# rs485.net
KiCad netlist of a schematic drawn in EasyEDA
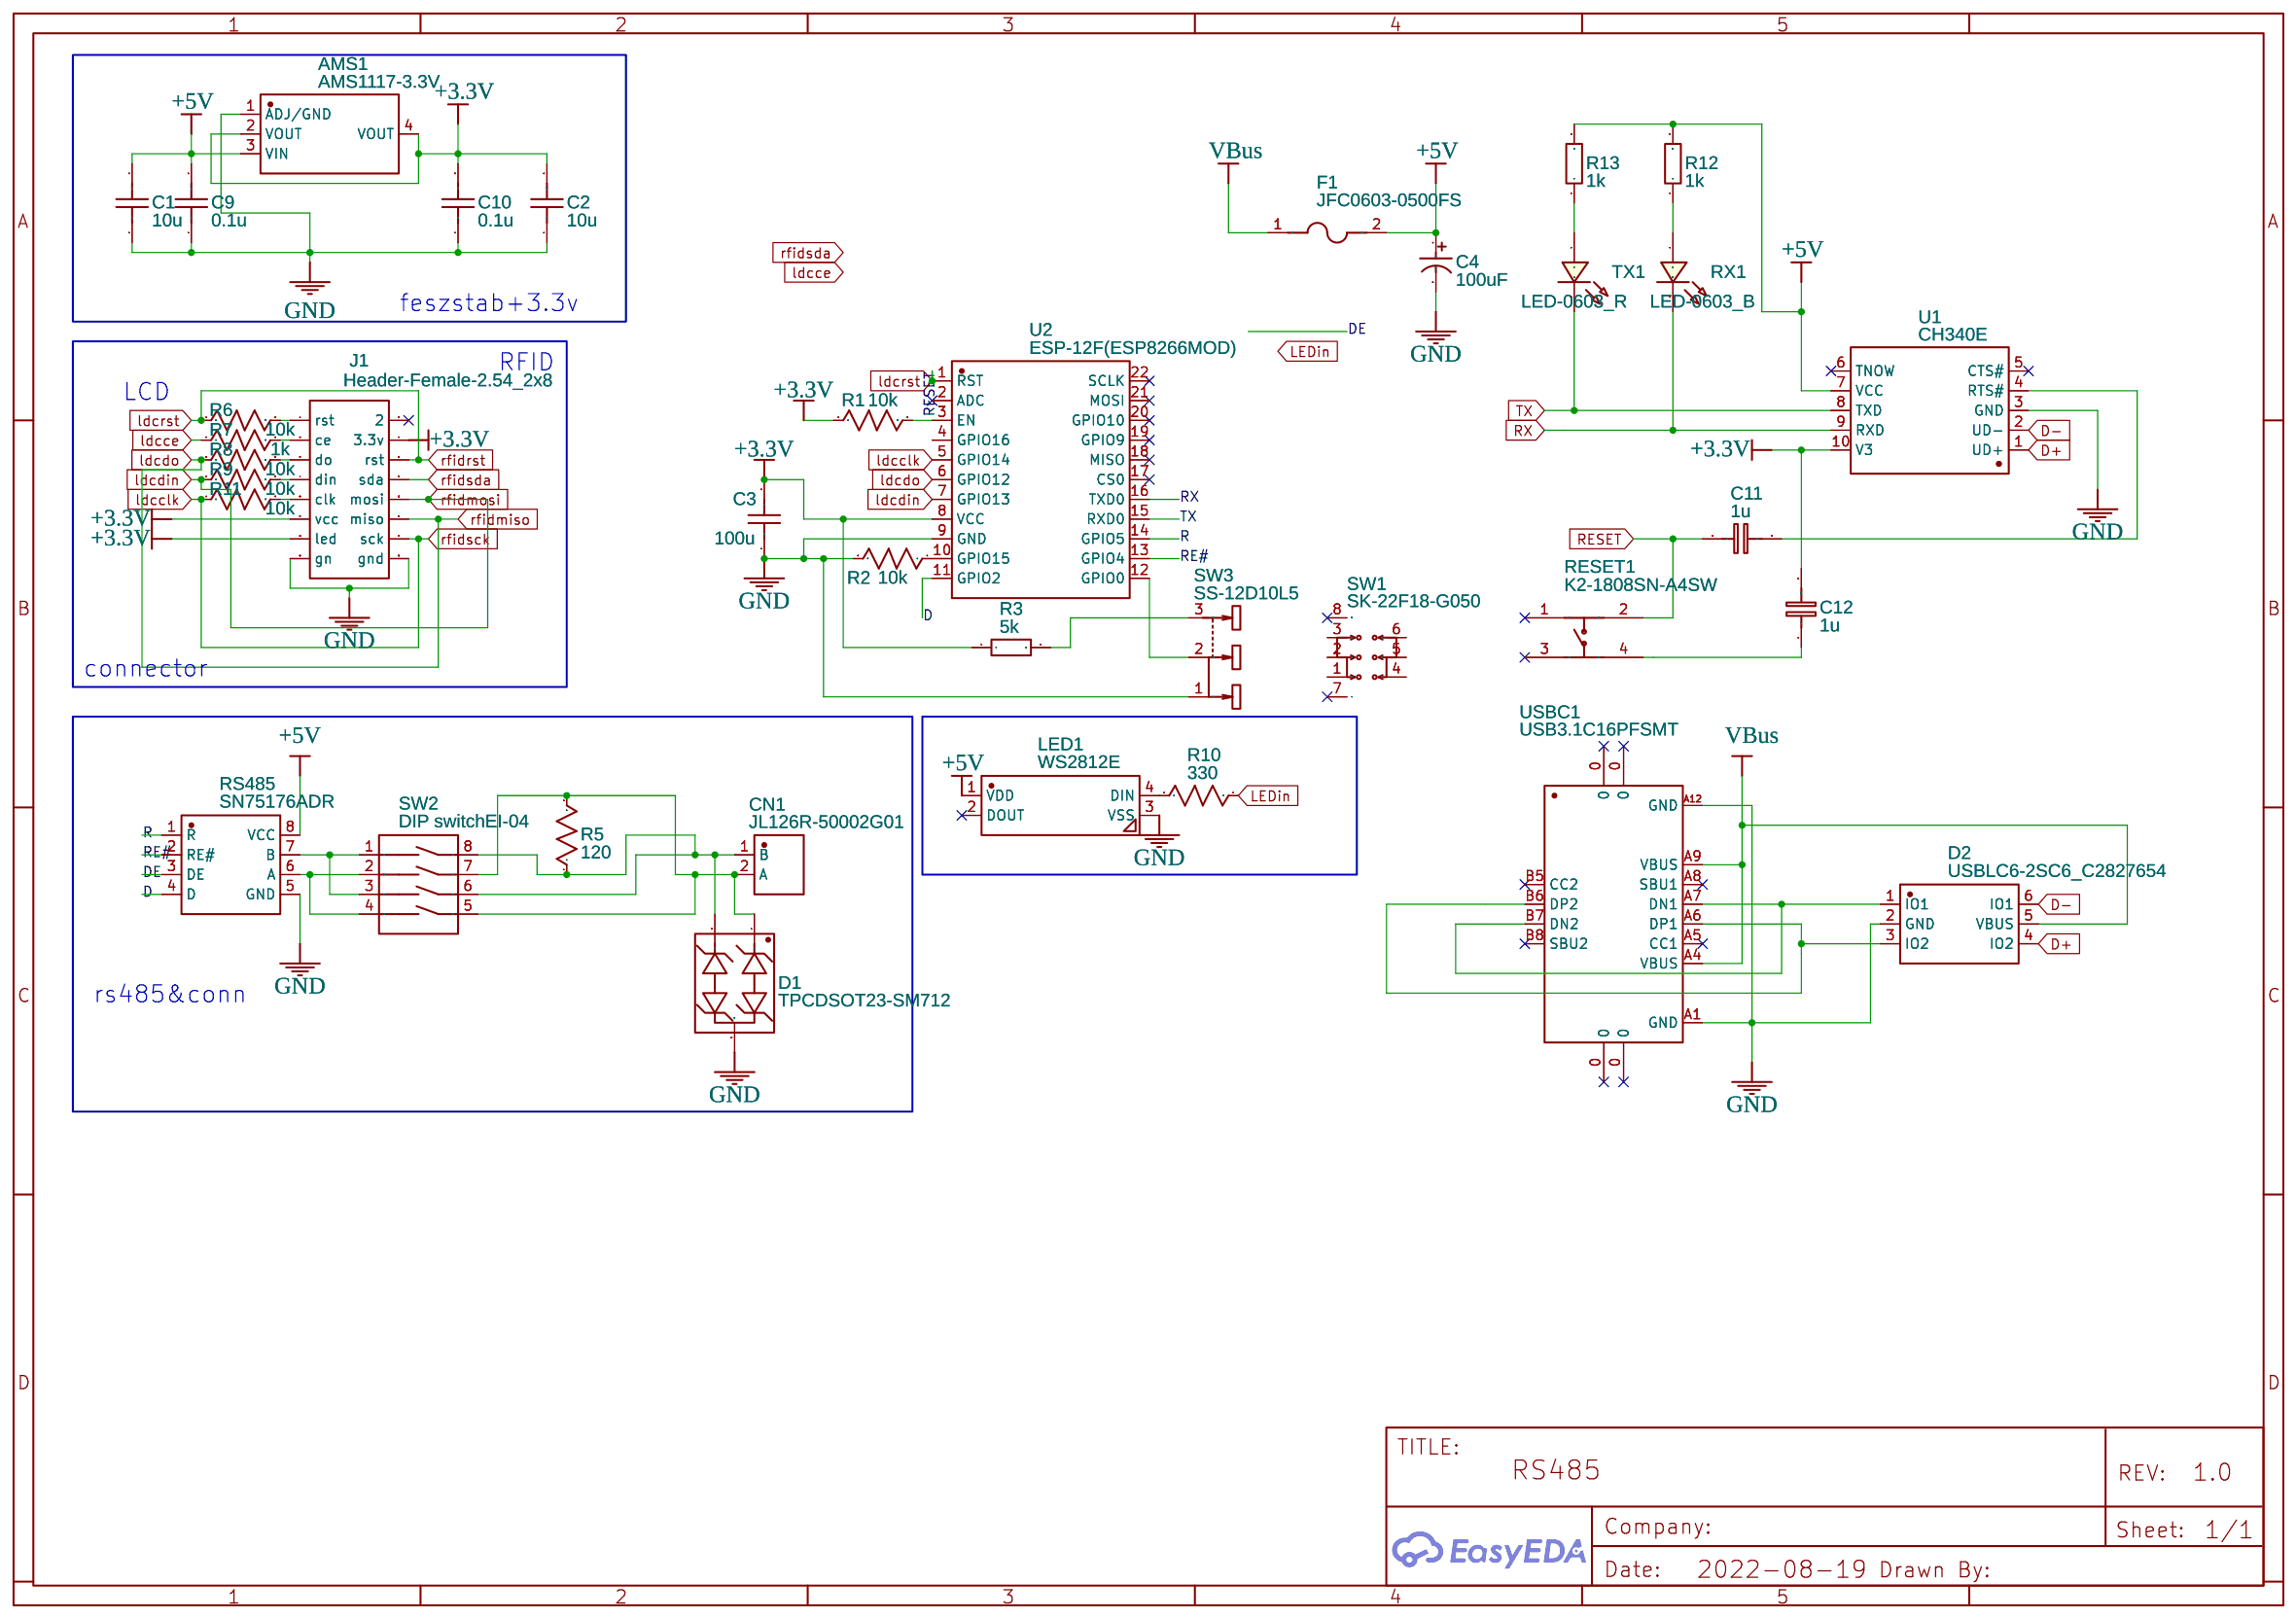
[diagram p0: schematic sheet]

(export (version "E")
  (design (tool "Eeschema 10.0.6"))
  (components
    (comp (ref "AMS1")
      (value "AMS1117-3.3V")
      (fields (field (name "BOM_Supplier Part") "C2688239"))
      (libsource (lib "") (part "AMS1117-3.3V"))
    )
    (comp (ref "C1") (value "10u") (libsource (lib "") (part "C_0603_US")))
    (comp (ref "C2") (value "10u") (libsource (lib "") (part "C_0603_US")))
    (comp (ref "C3") (value "100u") (libsource (lib "") (part "C_0603_US")))
    (comp (ref "C4")
      (value "100uF")
      (fields
        (field (name "BOM_Manufacturer Part") "RVT1A101M0505")
        (field (name "BOM_Supplier Part") "C3347")
      )
      (libsource (lib "") (part "RVT1A101M0505-C3347"))
    )
    (comp (ref "C9") (value "0.1u") (libsource (lib "") (part "C_0603_US")))
    (comp (ref "C10") (value "0.1u") (libsource (lib "") (part "C_0603_US")))
    (comp (ref "C11")
      (value "1u")
      (fields (field (name "BOM_Manufacturer Part") "?"))
      (libsource (lib "") (part "Cap_0603_EU_1"))
    )
    (comp (ref "C12")
      (value "1u")
      (fields (field (name "BOM_Manufacturer Part") "?"))
      (libsource (lib "") (part "Cap_0603_EU"))
    )
    (comp (ref "CN1")
      (value "JL126R-50002G01")
      (fields (field (name "BOM_Supplier Part") "C415452"))
      (libsource (lib "") (part "JL126R-50002G01"))
    )
    (comp (ref "D1")
      (value "TPCDSOT23-SM712")
      (fields (field (name "BOM_Supplier Part") "C558433"))
      (libsource (lib "") (part "TPCDSOT23-SM712"))
    )
    (comp (ref "D2")
      (value "USBLC6-2SC6_C2827654")
      (fields
        (field (name "BOM_Manufacturer Part") "USBLC6-2SC6")
        (field (name "BOM_Supplier Part") "C2827654")
      )
      (libsource (lib "") (part "USBLC6-2SC6_C2827654"))
    )
    (comp (ref "F1")
      (value "JFC0603-0500FS")
      (fields (field (name "BOM_Supplier Part") "C136327"))
      (libsource (lib "") (part "JFC0603-0500FS"))
    )
    (comp (ref "J1")
      (value "Header-Female-2.54_2x8")
      (fields
        (field (name "BOM_Manufacturer Part") "2.54mm,2×8Double female header")
        (field (name "BOM_Supplier Part") "C30734")
      )
      (libsource (lib "") (part "Header-Female-2.54_2x8"))
    )
    (comp (ref "LED1")
      (value "WS2812E")
      (fields (field (name "BOM_Supplier Part") "C139127"))
      (libsource (lib "") (part "WS2812E"))
    )
    (comp (ref "R1") (value "10k") (libsource (lib "") (part "R_0603_US_1")))
    (comp (ref "R2") (value "10k") (libsource (lib "") (part "R_0603_US")))
    (comp (ref "R3")
      (value "5k")
      (fields
        (field (name "BOM_Manufacturer Part") "RS-03K102JT")
        (field (name "BOM_Supplier Part") "C73797")
      )
      (libsource (lib "") (part "RS-03K102JT_1"))
    )
    (comp (ref "R5") (value "120") (libsource (lib "") (part "R_0603_US_2")))
    (comp (ref "R6") (value "10k") (libsource (lib "") (part "R_0603_US_1")))
    (comp (ref "R7") (value "1k") (libsource (lib "") (part "R_0603_US_1")))
    (comp (ref "R8") (value "10k") (libsource (lib "") (part "R_0603_US_1")))
    (comp (ref "R9") (value "10k") (libsource (lib "") (part "R_0603_US_1")))
    (comp (ref "R10") (value "330") (libsource (lib "") (part "R_0603_US_1")))
    (comp (ref "R11") (value "10k") (libsource (lib "") (part "R_0603_US_1")))
    (comp (ref "R12")
      (value "1k")
      (fields
        (field (name "BOM_Manufacturer Part") "RS-03K102JT")
        (field (name "BOM_Supplier Part") "C73797")
      )
      (libsource (lib "") (part "RS-03K102JT"))
    )
    (comp (ref "R13")
      (value "1k")
      (fields
        (field (name "BOM_Manufacturer Part") "RS-03K102JT")
        (field (name "BOM_Supplier Part") "C73797")
      )
      (libsource (lib "") (part "RS-03K102JT"))
    )
    (comp (ref "RESET1")
      (value "K2-1808SN-A4SW")
      (fields (field (name "BOM_Supplier Part") "C92589"))
      (libsource (lib "") (part "K2-1808SN-A4SW"))
    )
    (comp (ref "RS485")
      (value "SN75176ADR")
      (fields (field (name "BOM_Supplier Part") "C468242"))
      (libsource (lib "") (part "SN75176ADR"))
    )
    (comp (ref "RX1")
      (value "LED-0603_B")
      (fields
        (field (name "BOM_Manufacturer Part") "19-217/BHC-ZL1M2RY/3T")
        (field (name "BOM_Supplier Part") "C72041")
      )
      (libsource (lib "") (part "LED-0603_B"))
    )
    (comp (ref "SW1")
      (value "SK-22F18-G050")
      (fields (field (name "BOM_Supplier Part") "C2848886"))
      (libsource (lib "") (part "SK-22F18-G050"))
    )
    (comp (ref "SW2")
      (value "DIP switchEI-04")
      (fields (field (name "BOM_Supplier Part") "C99987"))
      (libsource (lib "") (part "DIP switchEI-04"))
    )
    (comp (ref "SW3")
      (value "SS-12D10L5")
      (fields (field (name "BOM_Supplier Part") "C319012"))
      (libsource (lib "") (part "SS-12D10L5"))
    )
    (comp (ref "TX1")
      (value "LED-0603_R")
      (fields
        (field (name "BOM_Manufacturer Part") "19-217/R6C-AL1M2VY/3T")
        (field (name "BOM_Supplier Part") "C72044")
      )
      (libsource (lib "") (part "LED-0603_R"))
    )
    (comp (ref "U1")
      (value "CH340E")
      (fields (field (name "BOM_Supplier Part") "C99652"))
      (libsource (lib "") (part "CH340E"))
    )
    (comp (ref "U2")
      (value "ESP-12F(ESP8266MOD)")
      (fields (field (name "BOM_Supplier Part") "C82891"))
      (libsource (lib "") (part "ESP-12F(ESP8266MOD)"))
    )
    (comp (ref "USBC1")
      (value "USB3.1C16PFSMT")
      (fields (field (name "BOM_Supplier Part") "C167321"))
      (libsource (lib "") (part "USB3.1C16PFSMT"))
    )
  )
  (nets
    (net (code "1") (name "+3.3V") (class "Default")
      (node (ref "AMS1") (pin "2") (pinfunction "VOUT_2") (pintype "unspecified"))
      (node (ref "AMS1") (pin "4") (pinfunction "VOUT_4") (pintype "unspecified"))
      (node (ref "C10") (pin "2") (pinfunction "2_2") (pintype "unspecified"))
      (node (ref "C12") (pin "2") (pinfunction "2_2") (pintype "unspecified"))
      (node (ref "C2") (pin "2") (pinfunction "2_2") (pintype "unspecified"))
      (node (ref "C3") (pin "2") (pinfunction "2_2") (pintype "unspecified"))
      (node (ref "J1") (pin "11") (pinfunction "vcc_11") (pintype "input"))
      (node (ref "J1") (pin "13") (pinfunction "led_13") (pintype "input"))
      (node (ref "J1") (pin "4") (pinfunction "3.3v_4") (pintype "input"))
      (node (ref "R1") (pin "1") (pinfunction "1_1") (pintype "unspecified"))
      (node (ref "R3") (pin "1") (pinfunction "1_1") (pintype "input"))
      (node (ref "U1") (pin "10") (pinfunction "V3_10") (pintype "unspecified"))
      (node (ref "U2") (pin "8") (pinfunction "VCC_8") (pintype "unspecified"))
    )
    (net (code "2") (name "+5V") (class "Default")
      (node (ref "AMS1") (pin "3") (pinfunction "VIN_3") (pintype "unspecified"))
      (node (ref "C1") (pin "2") (pinfunction "2_2") (pintype "unspecified"))
      (node (ref "C4") (pin "1") (pinfunction "1_1") (pintype "input"))
      (node (ref "C9") (pin "2") (pinfunction "2_2") (pintype "unspecified"))
      (node (ref "F1") (pin "2") (pinfunction "2_2") (pintype "unspecified"))
      (node (ref "LED1") (pin "1") (pinfunction "VDD_1") (pintype "unspecified"))
      (node (ref "R12") (pin "2") (pinfunction "2_2") (pintype "input"))
      (node (ref "R13") (pin "2") (pinfunction "2_2") (pintype "input"))
      (node (ref "RS485") (pin "8") (pinfunction "VCC_8") (pintype "unspecified"))
      (node (ref "U1") (pin "7") (pinfunction "VCC_7") (pintype "unspecified"))
    )
    (net (code "3") (name "/D") (class "Default")
      (node (ref "RS485") (pin "4") (pinfunction "D_4") (pintype "unspecified"))
      (node (ref "U2") (pin "11") (pinfunction "GPIO2_11") (pintype "unspecified"))
    )
    (net (code "4") (name "/DE") (class "Default")
      (node (ref "RS485") (pin "3") (pinfunction "DE_3") (pintype "unspecified"))
    )
    (net (code "5") (name "/R") (class "Default")
      (node (ref "RS485") (pin "1") (pinfunction "R_1") (pintype "unspecified"))
      (node (ref "U2") (pin "14") (pinfunction "GPIO5_14") (pintype "unspecified"))
    )
    (net (code "6") (name "/RE#") (class "Default")
      (node (ref "RS485") (pin "2") (pinfunction "RE#_2") (pintype "unspecified"))
      (node (ref "U2") (pin "13") (pinfunction "GPIO4_13") (pintype "unspecified"))
    )
    (net (code "7") (name "D+") (class "Default")
      (node (ref "D2") (pin "4") (pinfunction "IO2_4") (pintype "unspecified"))
      (node (ref "U1") (pin "1") (pinfunction "UD+_1") (pintype "unspecified"))
    )
    (net (code "8") (name "D-") (class "Default")
      (node (ref "D2") (pin "6") (pinfunction "IO1_6") (pintype "unspecified"))
      (node (ref "U1") (pin "2") (pinfunction "UD-_2") (pintype "unspecified"))
    )
    (net (code "9") (name "GND") (class "Default")
      (node (ref "AMS1") (pin "1") (pinfunction "ADJ/GND_1") (pintype "unspecified"))
      (node (ref "C1") (pin "1") (pinfunction "1_1") (pintype "unspecified"))
      (node (ref "C10") (pin "1") (pinfunction "1_1") (pintype "unspecified"))
      (node (ref "C2") (pin "1") (pinfunction "1_1") (pintype "unspecified"))
      (node (ref "C3") (pin "1") (pinfunction "1_1") (pintype "unspecified"))
      (node (ref "C4") (pin "2") (pinfunction "2_2") (pintype "input"))
      (node (ref "C9") (pin "1") (pinfunction "1_1") (pintype "unspecified"))
      (node (ref "D1") (pin "3") (pinfunction "3_3") (pintype "unspecified"))
      (node (ref "D2") (pin "2") (pinfunction "GND_2") (pintype "unspecified"))
      (node (ref "J1") (pin "15") (pinfunction "gn_15") (pintype "input"))
      (node (ref "J1") (pin "16") (pinfunction "gnd_16") (pintype "input"))
      (node (ref "LED1") (pin "3") (pinfunction "VSS_3") (pintype "unspecified"))
      (node (ref "R2") (pin "2") (pinfunction "2_2") (pintype "unspecified"))
      (node (ref "RS485") (pin "5") (pinfunction "GND_5") (pintype "unspecified"))
      (node (ref "SW3") (pin "1") (pinfunction "1_1") (pintype "unspecified"))
      (node (ref "U1") (pin "3") (pinfunction "GND_3") (pintype "unspecified"))
      (node (ref "U2") (pin "9") (pinfunction "GND_9") (pintype "unspecified"))
      (node (ref "USBC1") (pin "A1") (pinfunction "GND_A1") (pintype "unspecified"))
      (node (ref "USBC1") (pin "A12") (pinfunction "GND_A12") (pintype "unspecified"))
    )
    (net (code "10") (name "LEDin") (class "Default")
      (node (ref "R10") (pin "2") (pinfunction "2_2") (pintype "unspecified"))
    )
    (net (code "11") (name "Net-(C12-Pad1)") (class "Default")
      (node (ref "C12") (pin "1") (pinfunction "1_1") (pintype "unspecified"))
      (node (ref "RESET1") (pin "4") (pinfunction "4_4") (pintype "unspecified"))
    )
    (net (code "12") (name "Net-(CN1-A)") (class "Default")
      (node (ref "CN1") (pin "2") (pinfunction "A_2") (pintype "unspecified"))
      (node (ref "D1") (pin "1") (pinfunction "1_1") (pintype "unspecified"))
      (node (ref "R5") (pin "2") (pinfunction "2_2") (pintype "unspecified"))
      (node (ref "SW2") (pin "5") (pinfunction "5_5") (pintype "unspecified"))
      (node (ref "SW2") (pin "7") (pinfunction "7_7") (pintype "unspecified"))
    )
    (net (code "13") (name "Net-(CN1-B)") (class "Default")
      (node (ref "CN1") (pin "1") (pinfunction "B_1") (pintype "unspecified"))
      (node (ref "D1") (pin "2") (pinfunction "2_2") (pintype "unspecified"))
      (node (ref "R5") (pin "1") (pinfunction "1_1") (pintype "unspecified"))
      (node (ref "SW2") (pin "6") (pinfunction "6_6") (pintype "unspecified"))
      (node (ref "SW2") (pin "8") (pinfunction "8_8") (pintype "unspecified"))
    )
    (net (code "14") (name "Net-(J1-ce)") (class "Default")
      (node (ref "J1") (pin "3") (pinfunction "ce_3") (pintype "input"))
      (node (ref "R7") (pin "2") (pinfunction "2_2") (pintype "unspecified"))
    )
    (net (code "15") (name "Net-(J1-clk)") (class "Default")
      (node (ref "J1") (pin "9") (pinfunction "clk_9") (pintype "input"))
      (node (ref "R11") (pin "2") (pinfunction "2_2") (pintype "unspecified"))
    )
    (net (code "16") (name "Net-(J1-din)") (class "Default")
      (node (ref "J1") (pin "7") (pinfunction "din_7") (pintype "input"))
      (node (ref "R9") (pin "2") (pinfunction "2_2") (pintype "unspecified"))
    )
    (net (code "17") (name "Net-(J1-do)") (class "Default")
      (node (ref "J1") (pin "5") (pinfunction "do_5") (pintype "input"))
      (node (ref "R8") (pin "2") (pinfunction "2_2") (pintype "unspecified"))
    )
    (net (code "18") (name "Net-(J1-rst-Pad1)") (class "Default")
      (node (ref "J1") (pin "1") (pinfunction "rst_1") (pintype "input"))
      (node (ref "R6") (pin "2") (pinfunction "2_2") (pintype "unspecified"))
    )
    (net (code "19") (name "Net-(LED1-DIN)") (class "Default")
      (node (ref "LED1") (pin "4") (pinfunction "DIN_4") (pintype "unspecified"))
      (node (ref "R10") (pin "1") (pinfunction "1_1") (pintype "unspecified"))
    )
    (net (code "20") (name "Net-(R3-Pad2)") (class "Default")
      (node (ref "R3") (pin "2") (pinfunction "2_2") (pintype "input"))
      (node (ref "SW3") (pin "3") (pinfunction "3_3") (pintype "unspecified"))
    )
    (net (code "21") (name "Net-(R12-Pad1)") (class "Default")
      (node (ref "R12") (pin "1") (pinfunction "1_1") (pintype "input"))
      (node (ref "RX1") (pin "1") (pinfunction "1_1") (pintype "unspecified"))
    )
    (net (code "22") (name "Net-(R13-Pad1)") (class "Default")
      (node (ref "R13") (pin "1") (pinfunction "1_1") (pintype "input"))
      (node (ref "TX1") (pin "1") (pinfunction "1_1") (pintype "unspecified"))
    )
    (net (code "23") (name "Net-(RS485-A)") (class "Default")
      (node (ref "RS485") (pin "6") (pinfunction "A_6") (pintype "unspecified"))
      (node (ref "SW2") (pin "2") (pinfunction "2_2") (pintype "unspecified"))
      (node (ref "SW2") (pin "4") (pinfunction "4_4") (pintype "unspecified"))
    )
    (net (code "24") (name "Net-(RS485-B)") (class "Default")
      (node (ref "RS485") (pin "7") (pinfunction "B_7") (pintype "unspecified"))
      (node (ref "SW2") (pin "1") (pinfunction "1_1") (pintype "unspecified"))
      (node (ref "SW2") (pin "3") (pinfunction "3_3") (pintype "unspecified"))
    )
    (net (code "25") (name "Net-(U1-RTS#)") (class "Default")
      (node (ref "C11") (pin "2") (pinfunction "2_2") (pintype "unspecified"))
      (node (ref "U1") (pin "4") (pinfunction "RTS#_4") (pintype "unspecified"))
    )
    (net (code "26") (name "Net-(U2-EN)") (class "Default")
      (node (ref "R1") (pin "2") (pinfunction "2_2") (pintype "unspecified"))
      (node (ref "U2") (pin "3") (pinfunction "EN_3") (pintype "unspecified"))
    )
    (net (code "27") (name "Net-(U2-GPIO0)") (class "Default")
      (node (ref "SW3") (pin "2") (pinfunction "2_2") (pintype "unspecified"))
      (node (ref "U2") (pin "12") (pinfunction "GPIO0_12") (pintype "unspecified"))
    )
    (net (code "28") (name "Net-(U2-GPIO15)") (class "Default")
      (node (ref "R2") (pin "1") (pinfunction "1_1") (pintype "unspecified"))
      (node (ref "U2") (pin "10") (pinfunction "GPIO15_10") (pintype "unspecified"))
    )
    (net (code "29") (name "Net-(USBC1-DN1)") (class "Default")
      (node (ref "D2") (pin "1") (pinfunction "IO1_1") (pintype "unspecified"))
      (node (ref "USBC1") (pin "A7") (pinfunction "DN1_A7") (pintype "unspecified"))
      (node (ref "USBC1") (pin "B7") (pinfunction "DN2_B7") (pintype "unspecified"))
    )
    (net (code "30") (name "Net-(USBC1-DP1)") (class "Default")
      (node (ref "D2") (pin "3") (pinfunction "IO2_3") (pintype "unspecified"))
      (node (ref "USBC1") (pin "A6") (pinfunction "DP1_A6") (pintype "unspecified"))
      (node (ref "USBC1") (pin "B6") (pinfunction "DP2_B6") (pintype "unspecified"))
    )
    (net (code "31") (name "RESET") (class "Default")
      (node (ref "C11") (pin "1") (pinfunction "1_1") (pintype "unspecified"))
      (node (ref "J1") (pin "6") (pinfunction "rst_6") (pintype "input"))
      (node (ref "R6") (pin "1") (pinfunction "1_1") (pintype "unspecified"))
      (node (ref "RESET1") (pin "2") (pinfunction "2_2") (pintype "unspecified"))
      (node (ref "U2") (pin "1") (pinfunction "RST_1") (pintype "unspecified"))
    )
    (net (code "32") (name "RX") (class "Default")
      (node (ref "RX1") (pin "2") (pinfunction "2_2") (pintype "unspecified"))
      (node (ref "U1") (pin "9") (pinfunction "RXD_9") (pintype "unspecified"))
      (node (ref "U2") (pin "16") (pinfunction "TXD0_16") (pintype "unspecified"))
    )
    (net (code "33") (name "TX") (class "Default")
      (node (ref "TX1") (pin "2") (pinfunction "2_2") (pintype "unspecified"))
      (node (ref "U1") (pin "8") (pinfunction "TXD_8") (pintype "unspecified"))
      (node (ref "U2") (pin "15") (pinfunction "RXD0_15") (pintype "unspecified"))
    )
    (net (code "34") (name "VBus") (class "Default")
      (node (ref "D2") (pin "5") (pinfunction "VBUS_5") (pintype "unspecified"))
      (node (ref "F1") (pin "1") (pinfunction "1_1") (pintype "unspecified"))
      (node (ref "USBC1") (pin "A4") (pinfunction "VBUS_A4") (pintype "unspecified"))
      (node (ref "USBC1") (pin "A9") (pinfunction "VBUS_A9") (pintype "unspecified"))
    )
    (net (code "35") (name "ldcce") (class "Default")
      (node (ref "R7") (pin "1") (pinfunction "1_1") (pintype "unspecified"))
    )
    (net (code "36") (name "ldcclk") (class "Default")
      (node (ref "J1") (pin "14") (pinfunction "sck_14") (pintype "input"))
      (node (ref "R11") (pin "1") (pinfunction "1_1") (pintype "unspecified"))
      (node (ref "U2") (pin "5") (pinfunction "GPIO14_5") (pintype "unspecified"))
    )
    (net (code "37") (name "ldcdin") (class "Default")
      (node (ref "J1") (pin "10") (pinfunction "mosi_10") (pintype "input"))
      (node (ref "R9") (pin "1") (pinfunction "1_1") (pintype "unspecified"))
      (node (ref "U2") (pin "7") (pinfunction "GPIO13_7") (pintype "unspecified"))
    )
    (net (code "38") (name "ldcdo") (class "Default")
      (node (ref "J1") (pin "12") (pinfunction "miso_12") (pintype "input"))
      (node (ref "R8") (pin "1") (pinfunction "1_1") (pintype "unspecified"))
      (node (ref "U2") (pin "6") (pinfunction "GPIO12_6") (pintype "unspecified"))
    )
    (net (code "39") (name "rfidsda") (class "Default")
      (node (ref "J1") (pin "8") (pinfunction "sda_8") (pintype "input"))
    )
    (net (code "40") (name "unconnected-(J1-Pad2)") (class "Default")
      (node (ref "J1") (pin "2") (pinfunction "2_2") (pintype "input+no_connect"))
    )
    (net (code "41") (name "unconnected-(LED1-DOUT-Pad2)") (class "Default")
      (node (ref "LED1") (pin "2") (pinfunction "DOUT_2") (pintype "unspecified+no_connect"))
    )
    (net (code "42") (name "unconnected-(RESET1-Pad1)") (class "Default")
      (node (ref "RESET1") (pin "1") (pinfunction "1_1") (pintype "unspecified+no_connect"))
    )
    (net (code "43") (name "unconnected-(RESET1-Pad3)") (class "Default")
      (node (ref "RESET1") (pin "3") (pinfunction "3_3") (pintype "unspecified+no_connect"))
    )
    (net (code "44") (name "unconnected-(SW1-Pad1)") (class "Default")
      (node (ref "SW1") (pin "1") (pinfunction "1_1") (pintype "unspecified"))
    )
    (net (code "45") (name "unconnected-(SW1-Pad2)") (class "Default")
      (node (ref "SW1") (pin "2") (pinfunction "2_2") (pintype "unspecified"))
    )
    (net (code "46") (name "unconnected-(SW1-Pad3)") (class "Default")
      (node (ref "SW1") (pin "3") (pinfunction "3_3") (pintype "unspecified"))
    )
    (net (code "47") (name "unconnected-(SW1-Pad4)") (class "Default")
      (node (ref "SW1") (pin "4") (pinfunction "4_4") (pintype "unspecified"))
    )
    (net (code "48") (name "unconnected-(SW1-Pad5)") (class "Default")
      (node (ref "SW1") (pin "5") (pinfunction "5_5") (pintype "unspecified"))
    )
    (net (code "49") (name "unconnected-(SW1-Pad6)") (class "Default")
      (node (ref "SW1") (pin "6") (pinfunction "6_6") (pintype "unspecified"))
    )
    (net (code "50") (name "unconnected-(SW1-Pad7)") (class "Default")
      (node (ref "SW1") (pin "7") (pinfunction "7_7") (pintype "unspecified+no_connect"))
    )
    (net (code "51") (name "unconnected-(SW1-Pad8)") (class "Default")
      (node (ref "SW1") (pin "8") (pinfunction "8_8") (pintype "unspecified+no_connect"))
    )
    (net (code "52") (name "unconnected-(U1-CTS#-Pad5)") (class "Default")
      (node (ref "U1") (pin "5") (pinfunction "CTS#_5") (pintype "unspecified+no_connect"))
    )
    (net (code "53") (name "unconnected-(U1-TNOW-Pad6)") (class "Default")
      (node (ref "U1") (pin "6") (pinfunction "TNOW_6") (pintype "unspecified+no_connect"))
    )
    (net (code "54") (name "unconnected-(U2-ADC-Pad2)") (class "Default")
      (node (ref "U2") (pin "2") (pinfunction "ADC_2") (pintype "unspecified+no_connect"))
    )
    (net (code "55") (name "unconnected-(U2-CS0-Pad17)") (class "Default")
      (node (ref "U2") (pin "17") (pinfunction "CS0_17") (pintype "unspecified+no_connect"))
    )
    (net (code "56") (name "unconnected-(U2-GPIO9-Pad19)") (class "Default")
      (node (ref "U2") (pin "19") (pinfunction "GPIO9_19") (pintype "unspecified+no_connect"))
    )
    (net (code "57") (name "unconnected-(U2-GPIO10-Pad20)") (class "Default")
      (node (ref "U2") (pin "20") (pinfunction "GPIO10_20") (pintype "unspecified+no_connect"))
    )
    (net (code "58") (name "unconnected-(U2-GPIO16-Pad4)") (class "Default")
      (node (ref "U2") (pin "4") (pinfunction "GPIO16_4") (pintype "unspecified"))
    )
    (net (code "59") (name "unconnected-(U2-MISO-Pad18)") (class "Default")
      (node (ref "U2") (pin "18") (pinfunction "MISO_18") (pintype "unspecified+no_connect"))
    )
    (net (code "60") (name "unconnected-(U2-MOSI-Pad21)") (class "Default")
      (node (ref "U2") (pin "21") (pinfunction "MOSI_21") (pintype "unspecified+no_connect"))
    )
    (net (code "61") (name "unconnected-(U2-SCLK-Pad22)") (class "Default")
      (node (ref "U2") (pin "22") (pinfunction "SCLK_22") (pintype "unspecified+no_connect"))
    )
    (net (code "62") (name "unconnected-(USBC1-CC1-PadA5)") (class "Default")
      (node (ref "USBC1") (pin "A5") (pinfunction "CC1_A5") (pintype "unspecified+no_connect"))
    )
    (net (code "63") (name "unconnected-(USBC1-CC2-PadB5)") (class "Default")
      (node (ref "USBC1") (pin "B5") (pinfunction "CC2_B5") (pintype "unspecified+no_connect"))
    )
    (net (code "64") (name "unconnected-(USBC1-Pad0)") (class "Default")
      (node (ref "USBC1") (pin "0") (pinfunction "0_0") (pintype "unspecified+no_connect"))
    )
    (net (code "65") (name "unconnected-(USBC1-Pad0)_1") (class "Default")
      (node (ref "USBC1") (pin "0") (pinfunction "0_0") (pintype "unspecified+no_connect"))
    )
    (net (code "66") (name "unconnected-(USBC1-Pad0)_2") (class "Default")
      (node (ref "USBC1") (pin "0") (pinfunction "0_0") (pintype "unspecified+no_connect"))
    )
    (net (code "67") (name "unconnected-(USBC1-Pad0)_3") (class "Default")
      (node (ref "USBC1") (pin "0") (pinfunction "0_0") (pintype "unspecified+no_connect"))
    )
    (net (code "68") (name "unconnected-(USBC1-SBU1-PadA8)") (class "Default")
      (node (ref "USBC1") (pin "A8") (pinfunction "SBU1_A8") (pintype "unspecified+no_connect"))
    )
    (net (code "69") (name "unconnected-(USBC1-SBU2-PadB8)") (class "Default")
      (node (ref "USBC1") (pin "B8") (pinfunction "SBU2_B8") (pintype "unspecified+no_connect"))
    )
  )
)
